# geiger_01.net
KiCad netlist of a schematic drawn in EAGLE
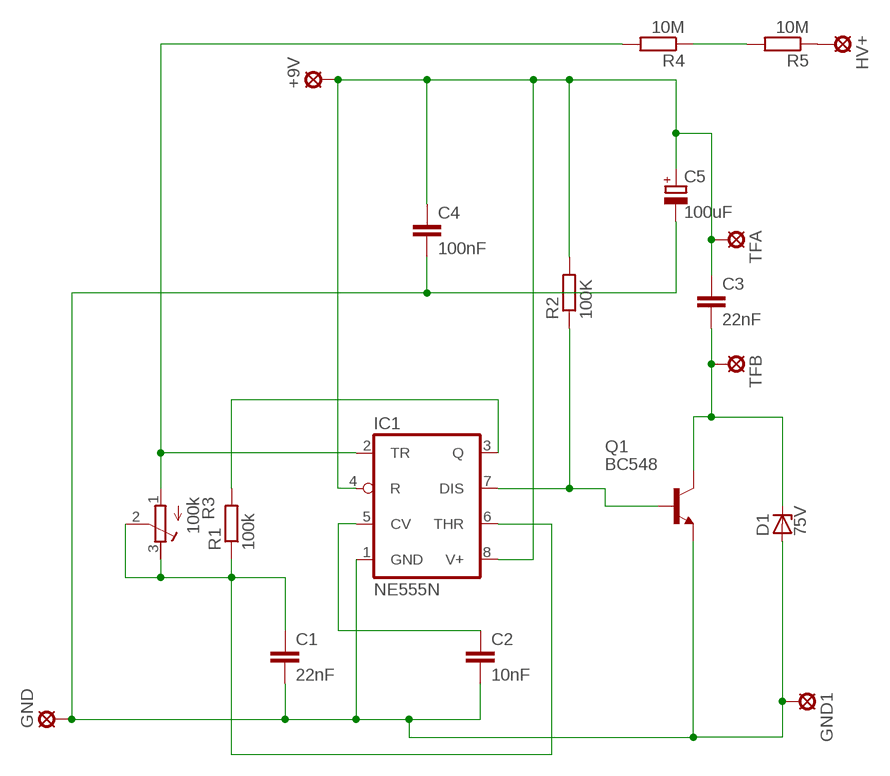
[diagram p0: schematic, sheet 1]

(export (version "E")
  (design (tool "Eeschema 10.0.6"))
  (components
    (comp (ref "+9V")
      (value "LSP10")
      (footprint "eagle-import:LSP10")
      (libsource (lib "eagle-import") (part "LSP10"))
    )
    (comp (ref "C1")
      (value "22nF")
      (footprint "eagle-import:C050-024X044")
      (libsource (lib "eagle-import") (part "C-EU050-024X044"))
    )
    (comp (ref "C2")
      (value "10nF")
      (footprint "eagle-import:C050-024X044")
      (libsource (lib "eagle-import") (part "C-EU050-024X044"))
    )
    (comp (ref "C3")
      (value "22nF")
      (footprint "eagle-import:C050-024X044")
      (libsource (lib "eagle-import") (part "C-EU050-024X044"))
    )
    (comp (ref "C4")
      (value "100nF")
      (footprint "eagle-import:C050-024X044")
      (libsource (lib "eagle-import") (part "C-EU050-024X044"))
    )
    (comp (ref "C5")
      (value "100uF")
      (footprint "eagle-import:E2,5-7")
      (libsource (lib "eagle-import") (part "CPOL-EUE2.5-7"))
    )
    (comp (ref "D1")
      (value "75V")
      (footprint "eagle-import:P1Z12")
      (libsource (lib "eagle-import") (part "ZENER-DIODEP1-Z12"))
    )
    (comp (ref "GND")
      (value "LSP10")
      (footprint "eagle-import:LSP10")
      (libsource (lib "eagle-import") (part "LSP10"))
    )
    (comp (ref "GND1")
      (value "LSP10")
      (footprint "eagle-import:LSP10")
      (libsource (lib "eagle-import") (part "LSP10"))
    )
    (comp (ref "HV+")
      (value "LSP10")
      (footprint "eagle-import:LSP10")
      (libsource (lib "eagle-import") (part "LSP10"))
    )
    (comp (ref "IC1")
      (value "NE555N")
      (footprint "eagle-import:DIL08")
      (libsource (lib "eagle-import") (part "555NNE"))
    )
    (comp (ref "Q1")
      (value "BC548")
      (footprint "eagle-import:TO92-EBC")
      (libsource (lib "eagle-import") (part "BC548"))
    )
    (comp (ref "R1")
      (value "100k")
      (footprint "eagle-import:0207_12")
      (libsource (lib "eagle-import") (part "R-EU_0207/12"))
    )
    (comp (ref "R2")
      (value "100K")
      (footprint "eagle-import:0207_12")
      (libsource (lib "eagle-import") (part "R-EU_0207/12"))
    )
    (comp (ref "R3")
      (value "100k")
      (footprint "eagle-import:RTRIM3339P")
      (libsource (lib "eagle-import") (part "R-TRIMM3339P"))
    )
    (comp (ref "R4")
      (value "10M")
      (footprint "eagle-import:0207_12")
      (libsource (lib "eagle-import") (part "R-EU_0207/12"))
    )
    (comp (ref "R5")
      (value "10M")
      (footprint "eagle-import:0207_12")
      (libsource (lib "eagle-import") (part "R-EU_0207/12"))
    )
    (comp (ref "TFA")
      (value "LSP10")
      (footprint "eagle-import:LSP10")
      (libsource (lib "eagle-import") (part "LSP10"))
    )
    (comp (ref "TFB")
      (value "LSP10")
      (footprint "eagle-import:LSP10")
      (libsource (lib "eagle-import") (part "LSP10"))
    )
  )
  (nets
    (net (code "1") (name "Net-(C3-Pad2)") (class "Default")
      (node (ref "C3") (pin "2") (pinfunction "2_2") (pintype "passive"))
      (node (ref "D1") (pin "C") (pinfunction "C_C") (pintype "passive"))
      (node (ref "Q1") (pin "C") (pinfunction "C_C") (pintype "passive"))
      (node (ref "TFB") (pin "MP") (pinfunction "MP_MP") (pintype "passive"))
    )
    (net (code "2") (name "Net-(HV+-PadMP)") (class "Default")
      (node (ref "HV+") (pin "MP") (pinfunction "MP_MP") (pintype "passive"))
      (node (ref "R5") (pin "1") (pinfunction "1_1") (pintype "passive"))
    )
    (net (code "3") (name "Net-(IC1-CV)") (class "Default")
      (node (ref "C2") (pin "1") (pinfunction "1_1") (pintype "passive"))
      (node (ref "IC1") (pin "5") (pinfunction "CV_5") (pintype "input"))
    )
    (net (code "4") (name "Net-(IC1-DIS)") (class "Default")
      (node (ref "IC1") (pin "7") (pinfunction "DIS_7") (pintype "input"))
      (node (ref "Q1") (pin "B") (pinfunction "B_B") (pintype "passive"))
      (node (ref "R2") (pin "1") (pinfunction "1_1") (pintype "passive"))
    )
    (net (code "5") (name "Net-(IC1-GND)") (class "Default")
      (node (ref "C1") (pin "2") (pinfunction "2_2") (pintype "passive"))
      (node (ref "C2") (pin "2") (pinfunction "2_2") (pintype "passive"))
      (node (ref "C4") (pin "2") (pinfunction "2_2") (pintype "passive"))
      (node (ref "C5") (pin "-") (pinfunction "-_-") (pintype "passive"))
      (node (ref "D1") (pin "A") (pinfunction "A_A") (pintype "passive"))
      (node (ref "GND") (pin "MP") (pinfunction "MP_MP") (pintype "passive"))
      (node (ref "GND1") (pin "MP") (pinfunction "MP_MP") (pintype "passive"))
      (node (ref "IC1") (pin "1") (pinfunction "GND_1") (pintype "power_in"))
      (node (ref "Q1") (pin "E") (pinfunction "E_E") (pintype "passive"))
    )
    (net (code "6") (name "Net-(IC1-Q)") (class "Default")
      (node (ref "IC1") (pin "3") (pinfunction "Q_3") (pintype "output"))
      (node (ref "R1") (pin "2") (pinfunction "2_2") (pintype "passive"))
    )
    (net (code "7") (name "Net-(IC1-R)") (class "Default")
      (node (ref "+9V") (pin "MP") (pinfunction "MP_MP") (pintype "passive"))
      (node (ref "C3") (pin "1") (pinfunction "1_1") (pintype "passive"))
      (node (ref "C4") (pin "1") (pinfunction "1_1") (pintype "passive"))
      (node (ref "C5") (pin "+") (pinfunction "+_+") (pintype "passive"))
      (node (ref "IC1") (pin "4") (pinfunction "R_4") (pintype "input"))
      (node (ref "IC1") (pin "8") (pinfunction "V+_8") (pintype "power_in"))
      (node (ref "R2") (pin "2") (pinfunction "2_2") (pintype "passive"))
      (node (ref "TFA") (pin "MP") (pinfunction "MP_MP") (pintype "passive"))
    )
    (net (code "8") (name "Net-(IC1-THR)") (class "Default")
      (node (ref "C1") (pin "1") (pinfunction "1_1") (pintype "passive"))
      (node (ref "IC1") (pin "6") (pinfunction "THR_6") (pintype "input"))
      (node (ref "R1") (pin "1") (pinfunction "1_1") (pintype "passive"))
      (node (ref "R3") (pin "2") (pinfunction "S_2") (pintype "passive"))
      (node (ref "R3") (pin "3") (pinfunction "E_3") (pintype "passive"))
    )
    (net (code "9") (name "Net-(IC1-TR)") (class "Default")
      (node (ref "IC1") (pin "2") (pinfunction "TR_2") (pintype "input"))
      (node (ref "R3") (pin "1") (pinfunction "A_1") (pintype "passive"))
      (node (ref "R4") (pin "2") (pinfunction "2_2") (pintype "passive"))
    )
    (net (code "10") (name "Net-(R4-Pad1)") (class "Default")
      (node (ref "R4") (pin "1") (pinfunction "1_1") (pintype "passive"))
      (node (ref "R5") (pin "2") (pinfunction "2_2") (pintype "passive"))
    )
  )
)
